# rs232_usb.net
KiCad netlist of a schematic drawn in EAGLE
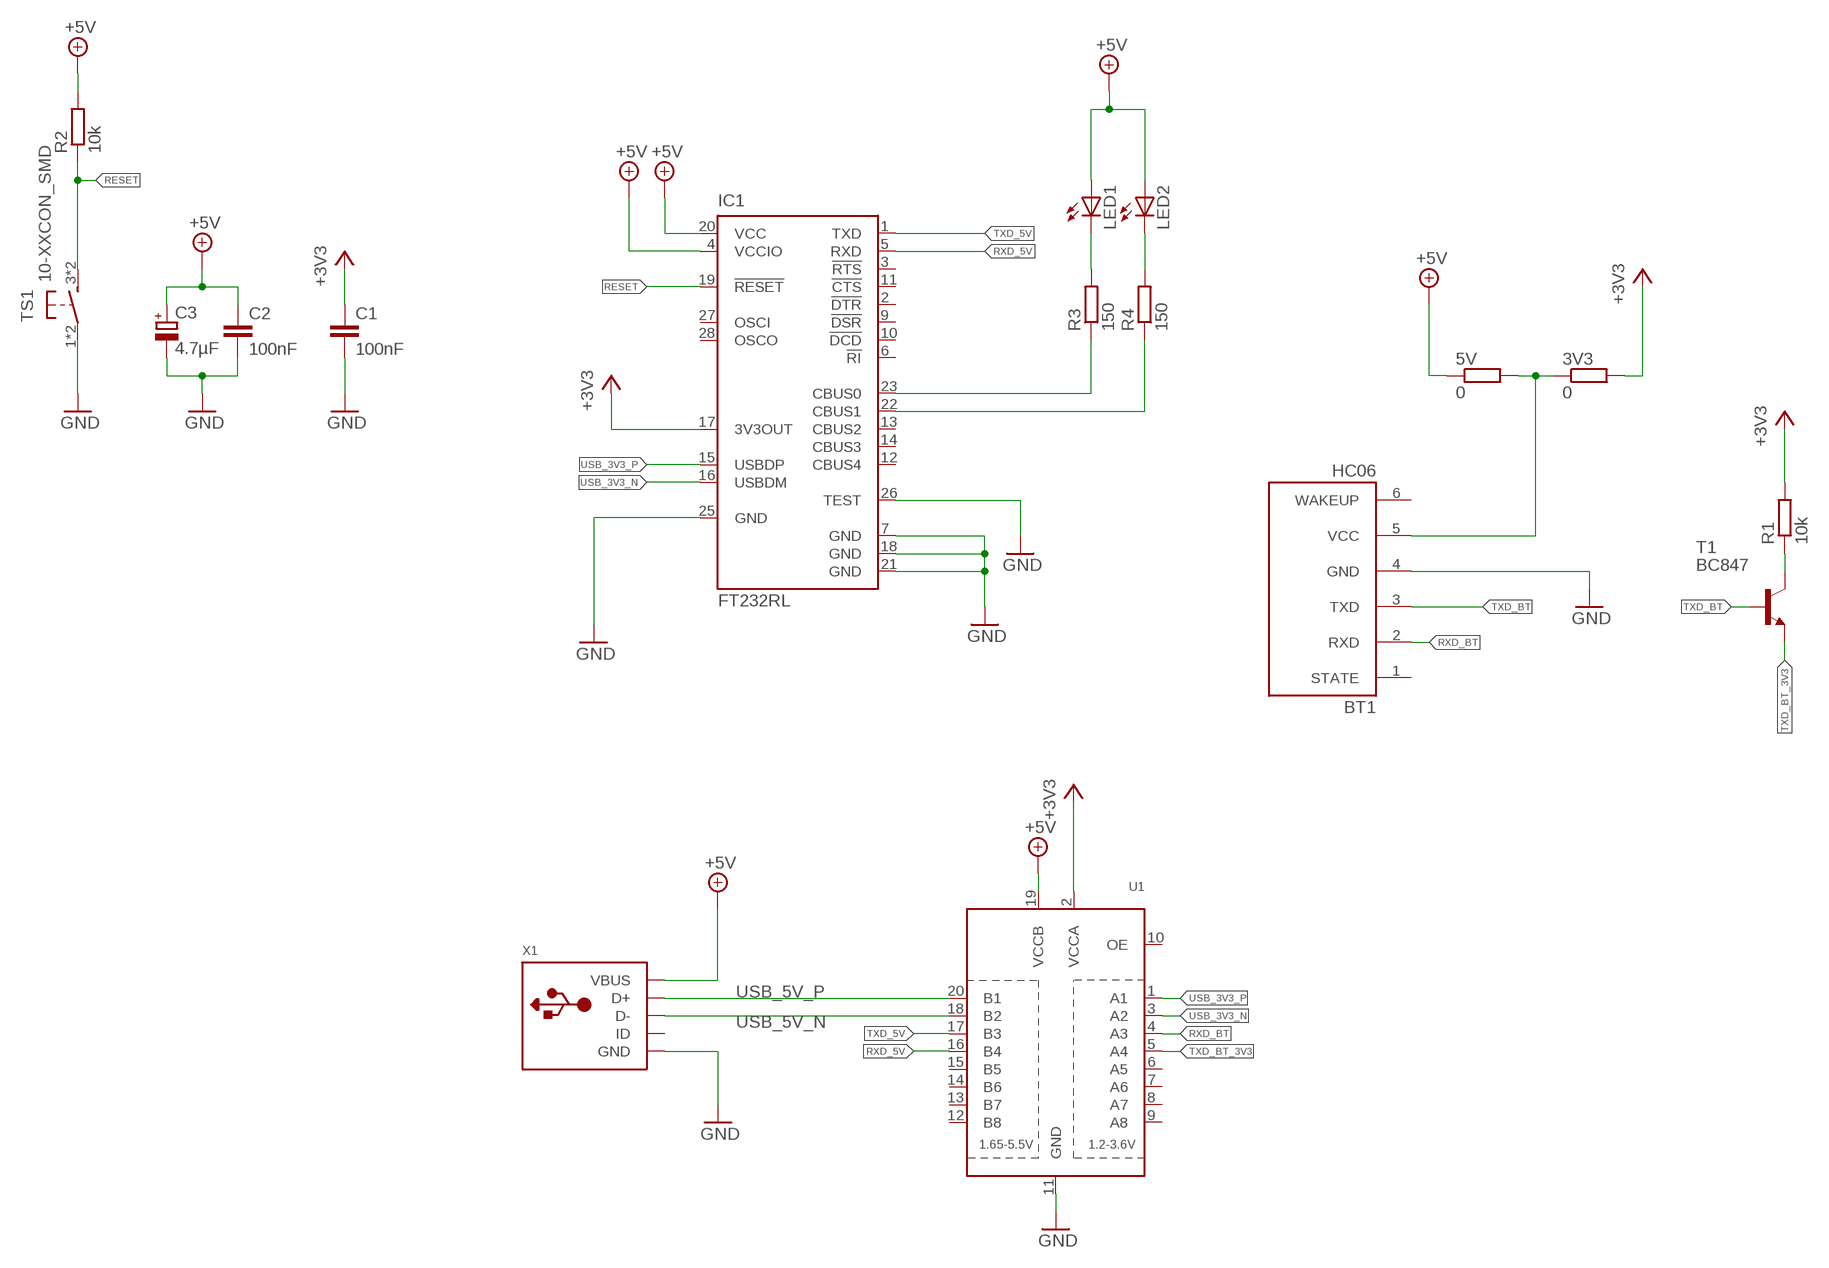
[diagram p0: schematic, sheet 1]

(export (version "E")
  (design (tool "Eeschema 10.0.6"))
  (components
    (comp (ref "3V3")
      (value "0")
      (footprint "eagle-import:R0805")
      (libsource (lib "eagle-import") (part "R-EU_R0805"))
    )
    (comp (ref "5V")
      (value "0")
      (footprint "eagle-import:R0805")
      (libsource (lib "eagle-import") (part "R-EU_R0805"))
    )
    (comp (ref "BT1")
      (value "HC06")
      (footprint "eagle-import:HC06")
      (libsource (lib "eagle-import") (part "HC06"))
    )
    (comp (ref "C1")
      (value "100nF")
      (footprint "eagle-import:C0805")
      (libsource (lib "eagle-import") (part "C-EUC0805"))
    )
    (comp (ref "C2")
      (value "100nF")
      (footprint "eagle-import:C0805")
      (libsource (lib "eagle-import") (part "C-EUC0805"))
    )
    (comp (ref "C3")
      (value "4.7µF")
      (footprint "eagle-import:C_6032-28R")
      (libsource (lib "eagle-import") (part "CPOL-EUC/6032-28R"))
    )
    (comp (ref "IC1")
      (value "FT232RL")
      (footprint "eagle-import:SSOP28")
      (libsource (lib "eagle-import") (part "FT232RL"))
    )
    (comp (ref "LED1")
      (value "LEDCHIPLED_0805")
      (footprint "eagle-import:CHIPLED_0805")
      (libsource (lib "eagle-import") (part "LEDCHIPLED_0805"))
    )
    (comp (ref "LED2")
      (value "LEDCHIPLED_0805")
      (footprint "eagle-import:CHIPLED_0805")
      (libsource (lib "eagle-import") (part "LEDCHIPLED_0805"))
    )
    (comp (ref "R1")
      (value "10k")
      (footprint "eagle-import:R0805")
      (libsource (lib "eagle-import") (part "R-EU_R0805"))
    )
    (comp (ref "R2")
      (value "10k")
      (footprint "eagle-import:R0805")
      (libsource (lib "eagle-import") (part "R-EU_R0805"))
    )
    (comp (ref "R3")
      (value "150")
      (footprint "eagle-import:R0805")
      (libsource (lib "eagle-import") (part "R-EU_R0805"))
    )
    (comp (ref "R4")
      (value "150")
      (footprint "eagle-import:R0805")
      (libsource (lib "eagle-import") (part "R-EU_R0805"))
    )
    (comp (ref "T1")
      (value "BC847")
      (footprint "eagle-import:SOT23")
      (libsource (lib "eagle-import") (part "BC847"))
    )
    (comp (ref "TS1")
      (value "10-XXCON_SMD")
      (footprint "eagle-import:SKHMPXE010")
      (libsource (lib "eagle-import") (part "10-XXCON_SMD"))
    )
    (comp (ref "U1")
      (value "TXB0108PWR")
      (footprint "eagle-import:TSSOP20")
      (libsource (lib "eagle-import") (part "TXB0108PWR"))
    )
    (comp (ref "X1")
      (value "USBMINIB")
      (footprint "eagle-import:USB-MINIB")
      (libsource (lib "eagle-import") (part "USBMINIB"))
    )
  )
  (nets
    (net (code "1") (name "+3V3") (class "Default")
      (node (ref "3V3") (pin "2") (pinfunction "2_2") (pintype "passive"))
      (node (ref "C1") (pin "1") (pinfunction "1_1") (pintype "passive"))
      (node (ref "IC1") (pin "17") (pinfunction "3V3OUT_17") (pintype "output"))
      (node (ref "R1") (pin "2") (pinfunction "2_2") (pintype "passive"))
      (node (ref "U1") (pin "2") (pinfunction "VCCA_2") (pintype "bidirectional"))
    )
    (net (code "2") (name "+5V") (class "Default")
      (node (ref "5V") (pin "1") (pinfunction "1_1") (pintype "passive"))
      (node (ref "C2") (pin "1") (pinfunction "1_1") (pintype "passive"))
      (node (ref "C3") (pin "+") (pinfunction "+_+") (pintype "passive"))
      (node (ref "IC1") (pin "20") (pinfunction "VCC_20") (pintype "power_in"))
      (node (ref "IC1") (pin "4") (pinfunction "VCCIO_4") (pintype "power_in"))
      (node (ref "LED1") (pin "A") (pinfunction "A_A") (pintype "passive"))
      (node (ref "LED2") (pin "A") (pinfunction "A_A") (pintype "passive"))
      (node (ref "R2") (pin "2") (pinfunction "2_2") (pintype "passive"))
      (node (ref "U1") (pin "19") (pinfunction "VCCB_19") (pintype "bidirectional"))
      (node (ref "X1") (pin "VBUS") (pinfunction "VBUS_VBUS") (pintype "power_in"))
    )
    (net (code "3") (name "/USB_5V_N") (class "Default")
      (node (ref "U1") (pin "18") (pinfunction "B2_18") (pintype "bidirectional"))
      (node (ref "X1") (pin "D-") (pinfunction "D-_D-") (pintype "bidirectional"))
    )
    (net (code "4") (name "/USB_5V_P") (class "Default")
      (node (ref "U1") (pin "20") (pinfunction "B1_20") (pintype "bidirectional"))
      (node (ref "X1") (pin "D+") (pinfunction "D+_D+") (pintype "bidirectional"))
    )
    (net (code "5") (name "GND") (class "Default")
      (node (ref "BT1") (pin "4") (pinfunction "GND_4") (pintype "power_in"))
      (node (ref "C1") (pin "2") (pinfunction "2_2") (pintype "passive"))
      (node (ref "C2") (pin "2") (pinfunction "2_2") (pintype "passive"))
      (node (ref "C3") (pin "-") (pinfunction "-_-") (pintype "passive"))
      (node (ref "IC1") (pin "18") (pinfunction "GND_18") (pintype "power_in"))
      (node (ref "IC1") (pin "21") (pinfunction "GND_21") (pintype "power_in"))
      (node (ref "IC1") (pin "25") (pinfunction "GND_25") (pintype "power_in"))
      (node (ref "IC1") (pin "26") (pinfunction "TEST_26") (pintype "input"))
      (node (ref "IC1") (pin "7") (pinfunction "GND_7") (pintype "power_in"))
      (node (ref "TS1") (pin "1") (pinfunction "P_1") (pintype "passive"))
      (node (ref "TS1") (pin "2") (pinfunction "P_2") (pintype "passive"))
      (node (ref "U1") (pin "11") (pinfunction "GND_11") (pintype "bidirectional"))
      (node (ref "X1") (pin "GND") (pinfunction "GND_GND") (pintype "power_in"))
    )
    (net (code "6") (name "Net-(BT1-VCC)") (class "Default")
      (node (ref "3V3") (pin "1") (pinfunction "1_1") (pintype "passive"))
      (node (ref "5V") (pin "2") (pinfunction "2_2") (pintype "passive"))
      (node (ref "BT1") (pin "5") (pinfunction "VCC_5") (pintype "power_in"))
    )
    (net (code "7") (name "Net-(IC1-CBUS0)") (class "Default")
      (node (ref "IC1") (pin "23") (pinfunction "CBUS0_23") (pintype "bidirectional"))
      (node (ref "R3") (pin "1") (pinfunction "1_1") (pintype "passive"))
    )
    (net (code "8") (name "Net-(IC1-CBUS1)") (class "Default")
      (node (ref "IC1") (pin "22") (pinfunction "CBUS1_22") (pintype "bidirectional"))
      (node (ref "R4") (pin "1") (pinfunction "1_1") (pintype "passive"))
    )
    (net (code "9") (name "Net-(LED1-PadC)") (class "Default")
      (node (ref "LED1") (pin "C") (pinfunction "C_C") (pintype "passive"))
      (node (ref "R3") (pin "2") (pinfunction "2_2") (pintype "passive"))
    )
    (net (code "10") (name "Net-(LED2-PadC)") (class "Default")
      (node (ref "LED2") (pin "C") (pinfunction "C_C") (pintype "passive"))
      (node (ref "R4") (pin "2") (pinfunction "2_2") (pintype "passive"))
    )
    (net (code "11") (name "Net-(T1-C)") (class "Default")
      (node (ref "R1") (pin "1") (pinfunction "1_1") (pintype "passive"))
      (node (ref "T1") (pin "3") (pinfunction "C_3") (pintype "passive"))
    )
    (net (code "12") (name "RESET") (class "Default")
      (node (ref "IC1") (pin "19") (pinfunction "~{RESET}_19") (pintype "input"))
      (node (ref "R2") (pin "1") (pinfunction "1_1") (pintype "passive"))
      (node (ref "TS1") (pin "3") (pinfunction "S_3") (pintype "passive"))
      (node (ref "TS1") (pin "4") (pinfunction "S_4") (pintype "passive"))
    )
    (net (code "13") (name "RXD_5V") (class "Default")
      (node (ref "IC1") (pin "5") (pinfunction "RXD_5") (pintype "input"))
      (node (ref "U1") (pin "16") (pinfunction "B4_16") (pintype "bidirectional"))
    )
    (net (code "14") (name "RXD_BT") (class "Default")
      (node (ref "BT1") (pin "2") (pinfunction "RXD_2") (pintype "input"))
      (node (ref "U1") (pin "4") (pinfunction "A3_4") (pintype "bidirectional"))
    )
    (net (code "15") (name "TXD_5V") (class "Default")
      (node (ref "IC1") (pin "1") (pinfunction "TXD_1") (pintype "output"))
      (node (ref "U1") (pin "17") (pinfunction "B3_17") (pintype "bidirectional"))
    )
    (net (code "16") (name "TXD_BT") (class "Default")
      (node (ref "BT1") (pin "3") (pinfunction "TXD_3") (pintype "output"))
      (node (ref "T1") (pin "1") (pinfunction "B_1") (pintype "passive"))
    )
    (net (code "17") (name "TXD_BT_3V3") (class "Default")
      (node (ref "T1") (pin "2") (pinfunction "E_2") (pintype "passive"))
      (node (ref "U1") (pin "5") (pinfunction "A4_5") (pintype "bidirectional"))
    )
    (net (code "18") (name "USB_3V3_N") (class "Default")
      (node (ref "IC1") (pin "16") (pinfunction "USBDM_16") (pintype "bidirectional"))
      (node (ref "U1") (pin "3") (pinfunction "A2_3") (pintype "bidirectional"))
    )
    (net (code "19") (name "USB_3V3_P") (class "Default")
      (node (ref "IC1") (pin "15") (pinfunction "USBDP_15") (pintype "bidirectional"))
      (node (ref "U1") (pin "1") (pinfunction "A1_1") (pintype "bidirectional"))
    )
    (net (code "20") (name "unconnected-(BT1-STATE-Pad1)") (class "Default")
      (node (ref "BT1") (pin "1") (pinfunction "STATE_1") (pintype "bidirectional"))
    )
    (net (code "21") (name "unconnected-(BT1-WAKEUP-Pad6)") (class "Default")
      (node (ref "BT1") (pin "6") (pinfunction "WAKEUP_6") (pintype "bidirectional"))
    )
    (net (code "22") (name "unconnected-(IC1-CBUS2-Pad13)") (class "Default")
      (node (ref "IC1") (pin "13") (pinfunction "CBUS2_13") (pintype "bidirectional"))
    )
    (net (code "23") (name "unconnected-(IC1-CBUS3-Pad14)") (class "Default")
      (node (ref "IC1") (pin "14") (pinfunction "CBUS3_14") (pintype "bidirectional"))
    )
    (net (code "24") (name "unconnected-(IC1-CBUS4-Pad12)") (class "Default")
      (node (ref "IC1") (pin "12") (pinfunction "CBUS4_12") (pintype "bidirectional"))
    )
    (net (code "25") (name "unconnected-(IC1-OSCI-Pad27)") (class "Default")
      (node (ref "IC1") (pin "27") (pinfunction "OSCI_27") (pintype "input"))
    )
    (net (code "26") (name "unconnected-(IC1-OSCO-Pad28)") (class "Default")
      (node (ref "IC1") (pin "28") (pinfunction "OSCO_28") (pintype "output"))
    )
    (net (code "27") (name "unconnected-(IC1-~{CTS}-Pad11)") (class "Default")
      (node (ref "IC1") (pin "11") (pinfunction "~{CTS}_11") (pintype "input"))
    )
    (net (code "28") (name "unconnected-(IC1-~{DCD}-Pad10)") (class "Default")
      (node (ref "IC1") (pin "10") (pinfunction "~{DCD}_10") (pintype "input"))
    )
    (net (code "29") (name "unconnected-(IC1-~{DSR}-Pad9)") (class "Default")
      (node (ref "IC1") (pin "9") (pinfunction "~{DSR}_9") (pintype "input"))
    )
    (net (code "30") (name "unconnected-(IC1-~{DTR}-Pad2)") (class "Default")
      (node (ref "IC1") (pin "2") (pinfunction "~{DTR}_2") (pintype "output"))
    )
    (net (code "31") (name "unconnected-(IC1-~{RI}-Pad6)") (class "Default")
      (node (ref "IC1") (pin "6") (pinfunction "~{RI}_6") (pintype "input"))
    )
    (net (code "32") (name "unconnected-(IC1-~{RTS}-Pad3)") (class "Default")
      (node (ref "IC1") (pin "3") (pinfunction "~{RTS}_3") (pintype "output"))
    )
    (net (code "33") (name "unconnected-(U1-A5-Pad6)") (class "Default")
      (node (ref "U1") (pin "6") (pinfunction "A5_6") (pintype "bidirectional"))
    )
    (net (code "34") (name "unconnected-(U1-A6-Pad7)") (class "Default")
      (node (ref "U1") (pin "7") (pinfunction "A6_7") (pintype "bidirectional"))
    )
    (net (code "35") (name "unconnected-(U1-A7-Pad8)") (class "Default")
      (node (ref "U1") (pin "8") (pinfunction "A7_8") (pintype "bidirectional"))
    )
    (net (code "36") (name "unconnected-(U1-A8-Pad9)") (class "Default")
      (node (ref "U1") (pin "9") (pinfunction "A8_9") (pintype "bidirectional"))
    )
    (net (code "37") (name "unconnected-(U1-B5-Pad15)") (class "Default")
      (node (ref "U1") (pin "15") (pinfunction "B5_15") (pintype "bidirectional"))
    )
    (net (code "38") (name "unconnected-(U1-B6-Pad14)") (class "Default")
      (node (ref "U1") (pin "14") (pinfunction "B6_14") (pintype "bidirectional"))
    )
    (net (code "39") (name "unconnected-(U1-B7-Pad13)") (class "Default")
      (node (ref "U1") (pin "13") (pinfunction "B7_13") (pintype "bidirectional"))
    )
    (net (code "40") (name "unconnected-(U1-B8-Pad12)") (class "Default")
      (node (ref "U1") (pin "12") (pinfunction "B8_12") (pintype "bidirectional"))
    )
    (net (code "41") (name "unconnected-(U1-OE-Pad10)") (class "Default")
      (node (ref "U1") (pin "10") (pinfunction "OE_10") (pintype "bidirectional"))
    )
    (net (code "42") (name "unconnected-(X1-PadID)") (class "Default")
      (node (ref "X1") (pin "ID") (pinfunction "ID_ID") (pintype "bidirectional"))
    )
  )
)
